# Sheet1-edgy.net
KiCad netlist of a schematic drawn in Altium Designer
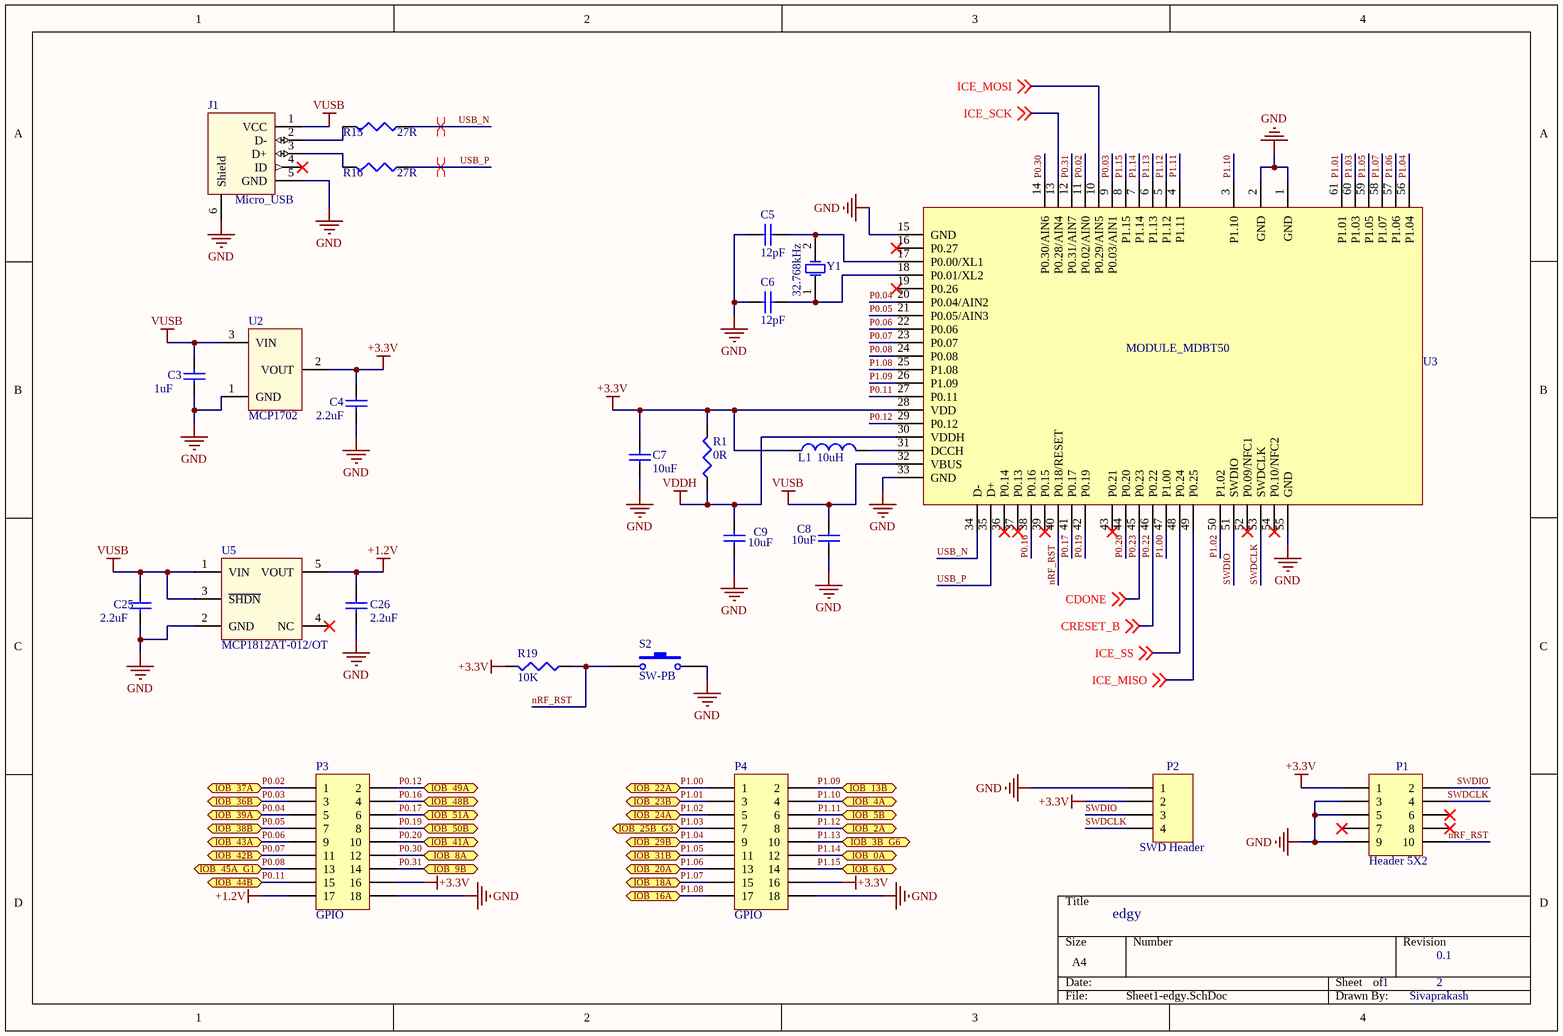
[diagram p0: Sheet1-edgy.SchDoc]

(export (version "E")
  (design (tool "Eeschema 10.0.6"))
  (components
    (comp (ref "C3")
      (value "1uF")
      (footprint "1608[0603]")
      (description "Capacitor (Semiconductor SIM Model)")
      (fields (field (name "PUBLISHER") "Altium Limited"))
      (libsource (lib "Miscellaneous Devices") (part "Cap Semi"))
    )
    (comp (ref "C4")
      (value "2.2uF")
      (footprint "1608[0603]")
      (description "Capacitor (Semiconductor SIM Model)")
      (fields (field (name "PUBLISHER") "Altium Limited"))
      (libsource (lib "Miscellaneous Devices") (part "Cap Semi"))
    )
    (comp (ref "C5")
      (value "12pF")
      (footprint "1608[0603]")
      (description "Capacitor (Semiconductor SIM Model)")
      (fields (field (name "PUBLISHER") "Altium Limited"))
      (libsource (lib "Miscellaneous Devices") (part "Cap Semi"))
    )
    (comp (ref "C6")
      (value "12pF")
      (footprint "1608[0603]")
      (description "Capacitor (Semiconductor SIM Model)")
      (fields (field (name "PUBLISHER") "Altium Limited"))
      (libsource (lib "Miscellaneous Devices") (part "Cap Semi"))
    )
    (comp (ref "C7")
      (value "10uF")
      (footprint "1608[0603]")
      (description "Capacitor (Semiconductor SIM Model)")
      (fields (field (name "PUBLISHER") "Altium Limited"))
      (libsource (lib "Miscellaneous Devices") (part "Cap Semi"))
    )
    (comp (ref "C8")
      (value "10uF")
      (footprint "1608[0603]")
      (description "Capacitor (Semiconductor SIM Model)")
      (fields (field (name "PUBLISHER") "Altium Limited"))
      (libsource (lib "Miscellaneous Devices") (part "Cap Semi"))
    )
    (comp (ref "C9")
      (value "10uF")
      (footprint "1608[0603]")
      (description "Capacitor (Semiconductor SIM Model)")
      (fields (field (name "PUBLISHER") "Altium Limited"))
      (libsource (lib "Miscellaneous Devices") (part "Cap Semi"))
    )
    (comp (ref "C25")
      (value "2.2uF")
      (footprint "1608[0603]")
      (description "Capacitor (Semiconductor SIM Model)")
      (fields (field (name "PUBLISHER") "Altium Limited"))
      (libsource (lib "Miscellaneous Devices") (part "Cap Semi"))
    )
    (comp (ref "C26")
      (value "2.2uF")
      (footprint "1608[0603]")
      (description "Capacitor (Semiconductor SIM Model)")
      (fields (field (name "PUBLISHER") "Altium Limited"))
      (libsource (lib "Miscellaneous Devices") (part "Cap Semi"))
    )
    (comp (ref "J1")
      (value "Micro_USB")
      (footprint "Micro_USB")
      (description "Micro USB 2.0")
      (libsource (lib "edgy") (part "Micro_USB"))
    )
    (comp (ref "L1")
      (value "10uH")
      (footprint "INDC1608L")
      (description "Inductor")
      (fields (field (name "PUBLISHER") "Altium Limited"))
      (libsource (lib "Miscellaneous Devices") (part "Inductor"))
    )
    (comp (ref "P1")
      (value "Header 5X2")
      (footprint "2x5_1.27mm_pitch_header")
      (description "Header, 5-Pin, Dual row")
      (fields (field (name "PUBLISHER") "Altium Limited"))
      (libsource (lib "Miscellaneous Connectors") (part "Header 5X2"))
    )
    (comp (ref "P2")
      (value "SWD Header")
      (footprint "4pin_2.54mm_header")
      (description "Header, 4-Pin")
      (fields (field (name "PUBLISHER") "Altium Limited"))
      (libsource (lib "Miscellaneous Connectors") (part "Header 4"))
    )
    (comp (ref "P3")
      (value "GPIO")
      (footprint "2x9_2.54mm pitch_header")
      (description "Header, 9-Pin, Dual row")
      (fields (field (name "PUBLISHER") "Altium Limited"))
      (libsource (lib "Miscellaneous Connectors") (part "Header 9X2"))
    )
    (comp (ref "P4")
      (value "GPIO")
      (footprint "2x9_2.54mm pitch_header")
      (description "Header, 9-Pin, Dual row")
      (fields (field (name "PUBLISHER") "Altium Limited"))
      (libsource (lib "Miscellaneous Connectors") (part "Header 9X2"))
    )
    (comp (ref "R1")
      (value "0R")
      (footprint "J1-0603")
      (description "Resistor")
      (fields (field (name "PUBLISHER") "Altium Limited"))
      (libsource (lib "Miscellaneous Devices") (part "Res3"))
    )
    (comp (ref "R15")
      (value "27R")
      (footprint "J1-0603")
      (description "Resistor")
      (fields (field (name "PUBLISHER") "Altium Limited"))
      (libsource (lib "Miscellaneous Devices") (part "Res3"))
    )
    (comp (ref "R16")
      (value "27R")
      (footprint "J1-0603")
      (description "Resistor")
      (fields (field (name "PUBLISHER") "Altium Limited"))
      (libsource (lib "Miscellaneous Devices") (part "Res3"))
    )
    (comp (ref "R19")
      (value "10K")
      (footprint "J1-0603")
      (description "Resistor")
      (fields (field (name "PUBLISHER") "Altium Limited"))
      (libsource (lib "Miscellaneous Devices") (part "Res3"))
    )
    (comp (ref "S2")
      (value "SW-PB")
      (footprint "Tact_Switch")
      (description "Switch")
      (fields (field (name "PUBLISHER") "Altium Limited"))
      (libsource (lib "Miscellaneous Devices") (part "SW-PB"))
    )
    (comp (ref "U2")
      (value "MCP1702")
      (footprint "SOT-23")
      (description "3.3 V Low Quasient Current LDO")
      (libsource (lib "edgy") (part "MCP1702"))
    )
    (comp (ref "U3")
      (value "MODULE_MDBT50")
      (footprint "PCB_MDBT50_10.5X15.5")
      (description "MDBT50")
      (libsource (lib "pi_gateway_hat") (part "MODULE_MDBT50"))
    )
    (comp (ref "U5")
      (value "MCP1812AT-012/OT")
      (footprint "SOT23-5BN")
      (fields (field (name "MANUFACTURER") "Microchip"))
      (libsource (lib "edgy") (part "MCP1812AT-012/OT"))
    )
    (comp (ref "Y1")
      (value "32.768kHz")
      (footprint "32.768kHz_crystal")
      (description "Crystal Oscillator")
      (fields (field (name "PUBLISHER") "Altium Limited"))
      (libsource (lib "Miscellaneous Devices") (part "XTAL"))
    )
  )
  (nets
    (net (code "1") (name "+1.2V") (class "Default")
      (node (ref "C26") (pin "2") (pinfunction "2_2") (pintype "passive"))
      (node (ref "P3") (pin "17") (pinfunction "17_17") (pintype "passive"))
      (node (ref "U5") (pin "5") (pinfunction "VOUT_5") (pintype "power_in"))
    )
    (net (code "2") (name "+3.3V") (class "Default")
      (node (ref "C4") (pin "2") (pinfunction "2_2") (pintype "passive"))
      (node (ref "C7") (pin "2") (pinfunction "2_2") (pintype "passive"))
      (node (ref "L1") (pin "1") (pinfunction "1_1") (pintype "passive"))
      (node (ref "P1") (pin "1") (pinfunction "1_1") (pintype "passive"))
      (node (ref "P2") (pin "2") (pinfunction "2_2") (pintype "passive"))
      (node (ref "P3") (pin "16") (pinfunction "16_16") (pintype "passive"))
      (node (ref "P4") (pin "16") (pinfunction "16_16") (pintype "passive"))
      (node (ref "R1") (pin "2") (pinfunction "2_2") (pintype "passive"))
      (node (ref "R19") (pin "2") (pinfunction "2_2") (pintype "passive"))
      (node (ref "U2") (pin "2") (pinfunction "VOUT_2") (pintype "power_in"))
      (node (ref "U3") (pin "28") (pinfunction "VDD_28") (pintype "passive"))
    )
    (net (code "3") (name "/P0.02") (class "Default")
      (node (ref "P3") (pin "1") (pinfunction "1_1") (pintype "passive"))
      (node (ref "U3") (pin "11") (pinfunction "P0.02/AIN0_11") (pintype "passive"))
    )
    (net (code "4") (name "/P0.03") (class "Default")
      (node (ref "P3") (pin "3") (pinfunction "3_3") (pintype "passive"))
      (node (ref "U3") (pin "9") (pinfunction "P0.03/AIN1_9") (pintype "passive"))
    )
    (net (code "5") (name "/P0.04") (class "Default")
      (node (ref "P3") (pin "5") (pinfunction "5_5") (pintype "passive"))
      (node (ref "U3") (pin "20") (pinfunction "P0.04/AIN2_20") (pintype "passive"))
    )
    (net (code "6") (name "/P0.05") (class "Default")
      (node (ref "P3") (pin "7") (pinfunction "7_7") (pintype "passive"))
      (node (ref "U3") (pin "21") (pinfunction "P0.05/AIN3_21") (pintype "passive"))
    )
    (net (code "7") (name "/P0.06") (class "Default")
      (node (ref "P3") (pin "9") (pinfunction "9_9") (pintype "passive"))
      (node (ref "U3") (pin "22") (pinfunction "P0.06_22") (pintype "passive"))
    )
    (net (code "8") (name "/P0.07") (class "Default")
      (node (ref "P3") (pin "11") (pinfunction "11_11") (pintype "passive"))
      (node (ref "U3") (pin "23") (pinfunction "P0.07_23") (pintype "passive"))
    )
    (net (code "9") (name "/P0.08") (class "Default")
      (node (ref "P3") (pin "13") (pinfunction "13_13") (pintype "passive"))
      (node (ref "U3") (pin "24") (pinfunction "P0.08_24") (pintype "passive"))
    )
    (net (code "10") (name "/P0.11") (class "Default")
      (node (ref "P3") (pin "15") (pinfunction "15_15") (pintype "passive"))
      (node (ref "U3") (pin "27") (pinfunction "P0.11_27") (pintype "passive"))
    )
    (net (code "11") (name "/P0.12") (class "Default")
      (node (ref "P3") (pin "2") (pinfunction "2_2") (pintype "passive"))
      (node (ref "U3") (pin "29") (pinfunction "P0.12_29") (pintype "passive"))
    )
    (net (code "12") (name "/P0.16") (class "Default")
      (node (ref "P3") (pin "4") (pinfunction "4_4") (pintype "passive"))
      (node (ref "U3") (pin "38") (pinfunction "P0.16_38") (pintype "passive"))
    )
    (net (code "13") (name "/P0.17") (class "Default")
      (node (ref "P3") (pin "6") (pinfunction "6_6") (pintype "passive"))
      (node (ref "U3") (pin "41") (pinfunction "P0.17_41") (pintype "passive"))
    )
    (net (code "14") (name "/P0.19") (class "Default")
      (node (ref "P3") (pin "8") (pinfunction "8_8") (pintype "passive"))
      (node (ref "U3") (pin "42") (pinfunction "P0.19_42") (pintype "passive"))
    )
    (net (code "15") (name "/P0.20") (class "Default")
      (node (ref "P3") (pin "10") (pinfunction "10_10") (pintype "passive"))
      (node (ref "U3") (pin "44") (pinfunction "P0.20_44") (pintype "passive"))
    )
    (net (code "16") (name "/P0.30") (class "Default")
      (node (ref "P3") (pin "12") (pinfunction "12_12") (pintype "passive"))
      (node (ref "U3") (pin "14") (pinfunction "P0.30/AIN6_14") (pintype "passive"))
    )
    (net (code "17") (name "/P0.31") (class "Default")
      (node (ref "P3") (pin "14") (pinfunction "14_14") (pintype "passive"))
      (node (ref "U3") (pin "12") (pinfunction "P0.31/AIN7_12") (pintype "passive"))
    )
    (net (code "18") (name "/P1.00") (class "Default")
      (node (ref "P4") (pin "1") (pinfunction "1_1") (pintype "passive"))
      (node (ref "U3") (pin "47") (pinfunction "P1.00_47") (pintype "passive"))
    )
    (net (code "19") (name "/P1.01") (class "Default")
      (node (ref "P4") (pin "3") (pinfunction "3_3") (pintype "passive"))
      (node (ref "U3") (pin "61") (pinfunction "P1.01_61") (pintype "passive"))
    )
    (net (code "20") (name "/P1.02") (class "Default")
      (node (ref "P4") (pin "5") (pinfunction "5_5") (pintype "passive"))
      (node (ref "U3") (pin "50") (pinfunction "P1.02_50") (pintype "passive"))
    )
    (net (code "21") (name "/P1.03") (class "Default")
      (node (ref "P4") (pin "7") (pinfunction "7_7") (pintype "passive"))
      (node (ref "U3") (pin "60") (pinfunction "P1.03_60") (pintype "passive"))
    )
    (net (code "22") (name "/P1.04") (class "Default")
      (node (ref "P4") (pin "9") (pinfunction "9_9") (pintype "passive"))
      (node (ref "U3") (pin "56") (pinfunction "P1.04_56") (pintype "passive"))
    )
    (net (code "23") (name "/P1.05") (class "Default")
      (node (ref "P4") (pin "11") (pinfunction "11_11") (pintype "passive"))
      (node (ref "U3") (pin "59") (pinfunction "P1.05_59") (pintype "passive"))
    )
    (net (code "24") (name "/P1.06") (class "Default")
      (node (ref "P4") (pin "13") (pinfunction "13_13") (pintype "passive"))
      (node (ref "U3") (pin "57") (pinfunction "P1.06_57") (pintype "passive"))
    )
    (net (code "25") (name "/P1.07") (class "Default")
      (node (ref "P4") (pin "15") (pinfunction "15_15") (pintype "passive"))
      (node (ref "U3") (pin "58") (pinfunction "P1.07_58") (pintype "passive"))
    )
    (net (code "26") (name "/P1.08") (class "Default")
      (node (ref "P4") (pin "17") (pinfunction "17_17") (pintype "passive"))
      (node (ref "U3") (pin "25") (pinfunction "P1.08_25") (pintype "passive"))
    )
    (net (code "27") (name "/P1.09") (class "Default")
      (node (ref "P4") (pin "2") (pinfunction "2_2") (pintype "passive"))
      (node (ref "U3") (pin "26") (pinfunction "P1.09_26") (pintype "passive"))
    )
    (net (code "28") (name "/P1.10") (class "Default")
      (node (ref "P4") (pin "4") (pinfunction "4_4") (pintype "passive"))
      (node (ref "U3") (pin "3") (pinfunction "P1.10_3") (pintype "passive"))
    )
    (net (code "29") (name "/P1.11") (class "Default")
      (node (ref "P4") (pin "6") (pinfunction "6_6") (pintype "passive"))
      (node (ref "U3") (pin "4") (pinfunction "P1.11_4") (pintype "passive"))
    )
    (net (code "30") (name "/P1.12") (class "Default")
      (node (ref "P4") (pin "8") (pinfunction "8_8") (pintype "passive"))
      (node (ref "U3") (pin "5") (pinfunction "P1.12_5") (pintype "passive"))
    )
    (net (code "31") (name "/P1.13") (class "Default")
      (node (ref "P4") (pin "10") (pinfunction "10_10") (pintype "passive"))
      (node (ref "U3") (pin "6") (pinfunction "P1.13_6") (pintype "passive"))
    )
    (net (code "32") (name "/P1.14") (class "Default")
      (node (ref "P4") (pin "12") (pinfunction "12_12") (pintype "passive"))
      (node (ref "U3") (pin "7") (pinfunction "P1.14_7") (pintype "passive"))
    )
    (net (code "33") (name "/P1.15") (class "Default")
      (node (ref "P4") (pin "14") (pinfunction "14_14") (pintype "passive"))
      (node (ref "U3") (pin "8") (pinfunction "P1.15_8") (pintype "passive"))
    )
    (net (code "34") (name "/SWDCLK") (class "Default")
      (node (ref "P1") (pin "4") (pinfunction "4_4") (pintype "passive"))
      (node (ref "P2") (pin "4") (pinfunction "4_4") (pintype "passive"))
      (node (ref "U3") (pin "53") (pinfunction "SWDCLK_53") (pintype "passive"))
    )
    (net (code "35") (name "/SWDIO") (class "Default")
      (node (ref "P1") (pin "2") (pinfunction "2_2") (pintype "passive"))
      (node (ref "P2") (pin "3") (pinfunction "3_3") (pintype "passive"))
      (node (ref "U3") (pin "51") (pinfunction "SWDIO_51") (pintype "passive"))
    )
    (net (code "36") (name "/USB_N") (class "Default")
      (node (ref "R15") (pin "1") (pinfunction "1_1") (pintype "passive"))
      (node (ref "U3") (pin "34") (pinfunction "D-_34") (pintype "passive"))
    )
    (net (code "37") (name "/USB_P") (class "Default")
      (node (ref "R16") (pin "1") (pinfunction "1_1") (pintype "passive"))
      (node (ref "U3") (pin "35") (pinfunction "D+_35") (pintype "passive"))
    )
    (net (code "38") (name "/nRF_RST") (class "Default")
      (node (ref "P1") (pin "10") (pinfunction "10_10") (pintype "passive"))
      (node (ref "R19") (pin "1") (pinfunction "1_1") (pintype "passive"))
      (node (ref "S2") (pin "1") (pinfunction "1_1") (pintype "passive"))
      (node (ref "U3") (pin "40") (pinfunction "P0.18/RESET_40") (pintype "passive"))
    )
    (net (code "39") (name "CDONE") (class "Default")
      (node (ref "U3") (pin "45") (pinfunction "P0.23_45") (pintype "passive"))
    )
    (net (code "40") (name "CRESET_B") (class "Default")
      (node (ref "U3") (pin "46") (pinfunction "P0.22_46") (pintype "passive"))
    )
    (net (code "41") (name "GND") (class "Default")
      (node (ref "C25") (pin "1") (pinfunction "1_1") (pintype "passive"))
      (node (ref "C26") (pin "1") (pinfunction "1_1") (pintype "passive"))
      (node (ref "C3") (pin "1") (pinfunction "1_1") (pintype "passive"))
      (node (ref "C4") (pin "1") (pinfunction "1_1") (pintype "passive"))
      (node (ref "C5") (pin "1") (pinfunction "1_1") (pintype "passive"))
      (node (ref "C6") (pin "1") (pinfunction "1_1") (pintype "passive"))
      (node (ref "C7") (pin "1") (pinfunction "1_1") (pintype "passive"))
      (node (ref "C8") (pin "1") (pinfunction "1_1") (pintype "passive"))
      (node (ref "C9") (pin "1") (pinfunction "1_1") (pintype "passive"))
      (node (ref "J1") (pin "5") (pinfunction "GND_5") (pintype "power_in"))
      (node (ref "J1") (pin "6") (pinfunction "Shield_6") (pintype "passive"))
      (node (ref "P1") (pin "3") (pinfunction "3_3") (pintype "passive"))
      (node (ref "P1") (pin "5") (pinfunction "5_5") (pintype "passive"))
      (node (ref "P1") (pin "9") (pinfunction "9_9") (pintype "passive"))
      (node (ref "P2") (pin "1") (pinfunction "1_1") (pintype "passive"))
      (node (ref "P3") (pin "18") (pinfunction "18_18") (pintype "passive"))
      (node (ref "P4") (pin "18") (pinfunction "18_18") (pintype "passive"))
      (node (ref "S2") (pin "2") (pinfunction "2_2") (pintype "passive"))
      (node (ref "U2") (pin "1") (pinfunction "GND_1") (pintype "power_in"))
      (node (ref "U3") (pin "1") (pinfunction "GND_1") (pintype "passive"))
      (node (ref "U3") (pin "15") (pinfunction "GND_15") (pintype "passive"))
      (node (ref "U3") (pin "2") (pinfunction "GND_2") (pintype "passive"))
      (node (ref "U3") (pin "33") (pinfunction "GND_33") (pintype "passive"))
      (node (ref "U3") (pin "55") (pinfunction "GND_55") (pintype "passive"))
      (node (ref "U5") (pin "2") (pinfunction "GND_2") (pintype "power_in"))
    )
    (net (code "42") (name "ICE_MISO") (class "Default")
      (node (ref "U3") (pin "49") (pinfunction "P0.25_49") (pintype "passive"))
    )
    (net (code "43") (name "ICE_MOSI") (class "Default")
      (node (ref "U3") (pin "10") (pinfunction "P0.29/AIN5_10") (pintype "passive"))
    )
    (net (code "44") (name "ICE_SCK") (class "Default")
      (node (ref "U3") (pin "13") (pinfunction "P0.28/AIN4_13") (pintype "passive"))
    )
    (net (code "45") (name "ICE_SS") (class "Default")
      (node (ref "U3") (pin "48") (pinfunction "P0.24_48") (pintype "passive"))
    )
    (net (code "46") (name "Net-(J1-D+)") (class "Default")
      (node (ref "J1") (pin "3") (pinfunction "D+_3") (pintype "bidirectional"))
      (node (ref "R16") (pin "2") (pinfunction "2_2") (pintype "passive"))
    )
    (net (code "47") (name "Net-(J1-D-)") (class "Default")
      (node (ref "J1") (pin "2") (pinfunction "D-_2") (pintype "bidirectional"))
      (node (ref "R15") (pin "2") (pinfunction "2_2") (pintype "passive"))
    )
    (net (code "48") (name "Net-(U3-DCCH)") (class "Default")
      (node (ref "L1") (pin "2") (pinfunction "2_2") (pintype "passive"))
      (node (ref "U3") (pin "31") (pinfunction "DCCH_31") (pintype "passive"))
    )
    (net (code "49") (name "Net-(U3-P0.00{slash}XL1)") (class "Default")
      (node (ref "C5") (pin "2") (pinfunction "2_2") (pintype "passive"))
      (node (ref "U3") (pin "17") (pinfunction "P0.00/XL1_17") (pintype "passive"))
      (node (ref "Y1") (pin "2") (pinfunction "OSC2_2") (pintype "passive"))
    )
    (net (code "50") (name "Net-(U3-P0.01{slash}XL2)") (class "Default")
      (node (ref "C6") (pin "2") (pinfunction "2_2") (pintype "passive"))
      (node (ref "U3") (pin "18") (pinfunction "P0.01/XL2_18") (pintype "passive"))
      (node (ref "Y1") (pin "1") (pinfunction "OSC1_1") (pintype "passive"))
    )
    (net (code "51") (name "VDDH") (class "Default")
      (node (ref "C9") (pin "2") (pinfunction "2_2") (pintype "passive"))
      (node (ref "R1") (pin "1") (pinfunction "1_1") (pintype "passive"))
      (node (ref "U3") (pin "30") (pinfunction "VDDH_30") (pintype "passive"))
    )
    (net (code "52") (name "VUSB") (class "Default")
      (node (ref "C25") (pin "2") (pinfunction "2_2") (pintype "passive"))
      (node (ref "C3") (pin "2") (pinfunction "2_2") (pintype "passive"))
      (node (ref "C8") (pin "2") (pinfunction "2_2") (pintype "passive"))
      (node (ref "J1") (pin "1") (pinfunction "VCC_1") (pintype "power_in"))
      (node (ref "U2") (pin "3") (pinfunction "VIN_3") (pintype "power_in"))
      (node (ref "U3") (pin "32") (pinfunction "VBUS_32") (pintype "passive"))
      (node (ref "U5") (pin "1") (pinfunction "VIN_1") (pintype "power_in"))
      (node (ref "U5") (pin "3") (pinfunction "~{SHDN}_3") (pintype "passive"))
    )
    (net (code "53") (name "unconnected-(J1-ID-Pad4)") (class "Default")
      (node (ref "J1") (pin "4") (pinfunction "ID_4") (pintype "output+no_connect"))
    )
    (net (code "54") (name "unconnected-(P1-Pad6)") (class "Default")
      (node (ref "P1") (pin "6") (pinfunction "6_6") (pintype "passive+no_connect"))
    )
    (net (code "55") (name "unconnected-(P1-Pad7)") (class "Default")
      (node (ref "P1") (pin "7") (pinfunction "7_7") (pintype "passive+no_connect"))
    )
    (net (code "56") (name "unconnected-(P1-Pad8)") (class "Default")
      (node (ref "P1") (pin "8") (pinfunction "8_8") (pintype "passive+no_connect"))
    )
    (net (code "57") (name "unconnected-(U3-P0.09{slash}NFC1-Pad52)") (class "Default")
      (node (ref "U3") (pin "52") (pinfunction "P0.09/NFC1_52") (pintype "passive+no_connect"))
    )
    (net (code "58") (name "unconnected-(U3-P0.10{slash}NFC2-Pad54)") (class "Default")
      (node (ref "U3") (pin "54") (pinfunction "P0.10/NFC2_54") (pintype "passive+no_connect"))
    )
    (net (code "59") (name "unconnected-(U3-P0.13-Pad37)") (class "Default")
      (node (ref "U3") (pin "37") (pinfunction "P0.13_37") (pintype "passive+no_connect"))
    )
    (net (code "60") (name "unconnected-(U3-P0.14-Pad36)") (class "Default")
      (node (ref "U3") (pin "36") (pinfunction "P0.14_36") (pintype "passive+no_connect"))
    )
    (net (code "61") (name "unconnected-(U3-P0.15-Pad39)") (class "Default")
      (node (ref "U3") (pin "39") (pinfunction "P0.15_39") (pintype "passive+no_connect"))
    )
    (net (code "62") (name "unconnected-(U3-P0.21-Pad43)") (class "Default")
      (node (ref "U3") (pin "43") (pinfunction "P0.21_43") (pintype "passive+no_connect"))
    )
    (net (code "63") (name "unconnected-(U3-P0.26-Pad19)") (class "Default")
      (node (ref "U3") (pin "19") (pinfunction "P0.26_19") (pintype "passive+no_connect"))
    )
    (net (code "64") (name "unconnected-(U3-P0.27-Pad16)") (class "Default")
      (node (ref "U3") (pin "16") (pinfunction "P0.27_16") (pintype "passive+no_connect"))
    )
    (net (code "65") (name "unconnected-(U5-NC-Pad4)") (class "Default")
      (node (ref "U5") (pin "4") (pinfunction "NC_4") (pintype "passive+no_connect"))
    )
  )
)
